# CH32V203C8T6-R1.net
KiCad netlist of a schematic drawn in Altium Designer
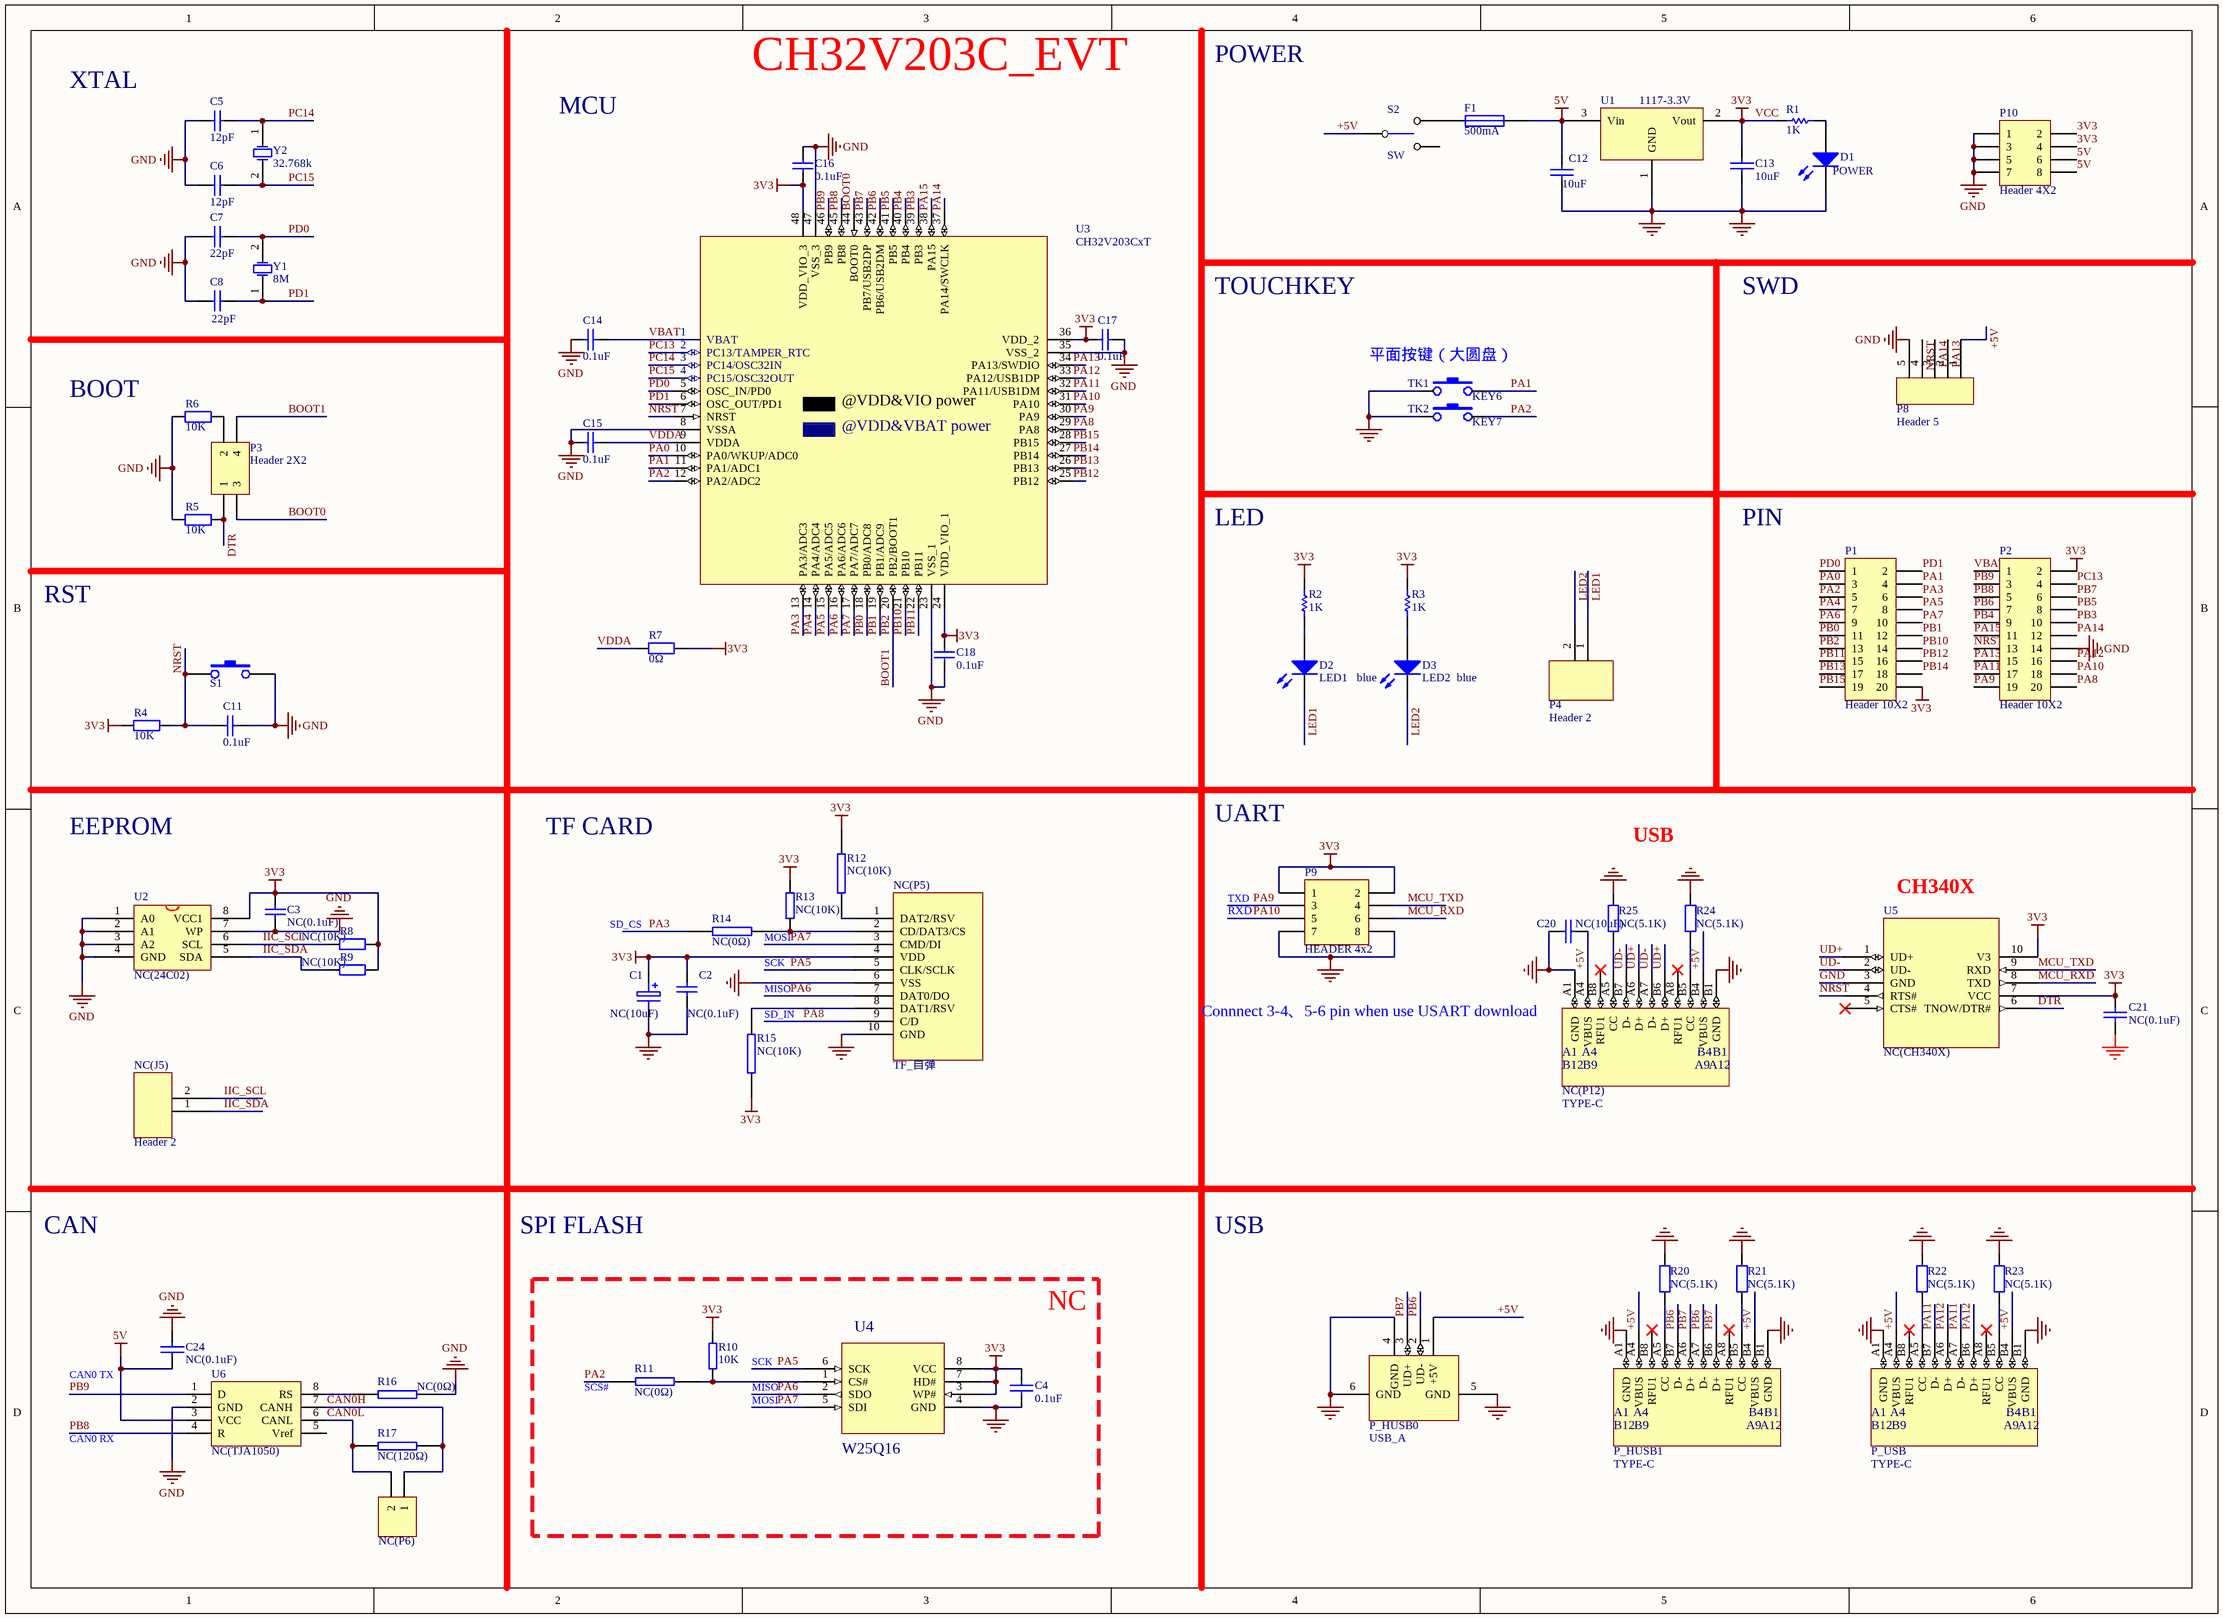
[diagram p0: CH32V203C8T6-R1.SchDoc]

(export (version "E")
  (design (tool "Eeschema 10.0.6"))
  (components
    (comp (ref "C1")
      (value "NC(10uF)")
      (footprint "3216")
      (description "Electrolytic Capacitor")
      (libsource (lib "*") (part "ELECTRO1"))
    )
    (comp (ref "C2")
      (value "NC(0.1uF)")
      (footprint "0603")
      (description "Capacitor")
      (fields (field (name "Comment") "0.1uF") (field (name "PUBLISHER") "Altium Limited"))
      (libsource (lib "*") (part "Cap"))
    )
    (comp (ref "C3")
      (value "NC(0.1uF)")
      (footprint "0603")
      (description "Capacitor")
      (fields (field (name "PUBLISHER") "Altium Limited"))
      (libsource (lib "Miscellaneous Devices") (part "Cap"))
    )
    (comp (ref "C4")
      (value "0.1uF")
      (footprint "0603")
      (description "Capacitor")
      (libsource (lib "") (part "CAP_1"))
    )
    (comp (ref "C5")
      (value "12pF")
      (footprint "0603")
      (description "Capacitor")
      (fields (field (name "PUBLISHER") "Altium Limited"))
      (libsource (lib "Miscellaneous Devices") (part "Cap"))
    )
    (comp (ref "C6")
      (value "12pF")
      (footprint "0603")
      (description "Capacitor")
      (fields (field (name "PUBLISHER") "Altium Limited"))
      (libsource (lib "Miscellaneous Devices") (part "Cap"))
    )
    (comp (ref "C7")
      (value "22pF")
      (footprint "0603")
      (description "Capacitor")
      (fields (field (name "PUBLISHER") "Altium Limited"))
      (libsource (lib "Miscellaneous Devices") (part "Cap"))
    )
    (comp (ref "C8")
      (value "22pF")
      (footprint "0603")
      (description "Capacitor")
      (fields (field (name "PUBLISHER") "Altium Limited"))
      (libsource (lib "Miscellaneous Devices") (part "Cap"))
    )
    (comp (ref "C11")
      (value "0.1uF")
      (footprint "0603")
      (description "Capacitor")
      (fields (field (name "PUBLISHER") "Altium Limited"))
      (libsource (lib "Miscellaneous Devices") (part "Cap"))
    )
    (comp (ref "C12")
      (value "10uF")
      (footprint "3216")
      (description "Capacitor")
      (libsource (lib "*") (part "CAP"))
    )
    (comp (ref "C13")
      (value "10uF")
      (footprint "0603")
      (description "Capacitor")
      (libsource (lib "*") (part "CAP"))
    )
    (comp (ref "C14")
      (value "0.1uF")
      (footprint "0603")
      (description "Capacitor")
      (fields (field (name "PUBLISHER") "Altium Limited"))
      (libsource (lib "Miscellaneous Devices") (part "Cap"))
    )
    (comp (ref "C15")
      (value "0.1uF")
      (footprint "0603")
      (description "Capacitor")
      (fields (field (name "PUBLISHER") "Altium Limited"))
      (libsource (lib "Miscellaneous Devices") (part "Cap"))
    )
    (comp (ref "C16")
      (value "0.1uF")
      (footprint "0603")
      (description "Capacitor")
      (fields (field (name "PUBLISHER") "Altium Limited"))
      (libsource (lib "Miscellaneous Devices") (part "Cap"))
    )
    (comp (ref "C17")
      (value "0.1uF")
      (footprint "0603")
      (description "Capacitor")
      (fields (field (name "PUBLISHER") "Altium Limited"))
      (libsource (lib "Miscellaneous Devices") (part "Cap"))
    )
    (comp (ref "C18")
      (value "0.1uF")
      (footprint "0603")
      (description "Capacitor")
      (fields (field (name "PUBLISHER") "Altium Limited"))
      (libsource (lib "Miscellaneous Devices") (part "Cap"))
    )
    (comp (ref "C20")
      (value "NC(10uF)")
      (footprint "3216_C")
      (description "Capacitor")
      (libsource (lib "*") (part "CAP"))
    )
    (comp (ref "C21")
      (value "NC(0.1uF)")
      (footprint "0603_C")
      (description "Capacitor")
      (libsource (lib "*") (part "CAP"))
    )
    (comp (ref "C24")
      (value "NC(0.1uF)")
      (footprint "0603")
      (description "Capacitor")
      (libsource (lib "") (part "CAP_1"))
    )
    (comp (ref "D1")
      (value "POWER")
      (footprint "0603L")
      (description "Typical INFRARED GaAs LED")
      (fields (field (name "PUBLISHER") "Altium Limited"))
      (libsource (lib "Miscellaneous Devices") (part "LED0"))
    )
    (comp (ref "D2")
      (value "LED1   blue")
      (footprint "0603L")
      (description "Typical INFRARED GaAs LED")
      (fields (field (name "PUBLISHER") "Altium Limited"))
      (libsource (lib "Miscellaneous Devices") (part "LED0"))
    )
    (comp (ref "D3")
      (value "LED2  blue")
      (footprint "0603L")
      (description "Typical INFRARED GaAs LED")
      (fields (field (name "PUBLISHER") "Altium Limited"))
      (libsource (lib "Miscellaneous Devices") (part "LED0"))
    )
    (comp (ref "F1")
      (value "500mA")
      (footprint "0603")
      (description "Fuse")
      (libsource (lib "*") (part "FUSE1"))
    )
    (comp (ref "NC(J5)") (value "Header 2") (footprint "SIP2 - 40mil") (libsource (lib "") (part "2HEAD_1")))
    (comp (ref "NC(P5)") (value "TF_自弹") (footprint "TF_CARD") (libsource (lib "*") (part "TF_自弹")))
    (comp (ref "NC(P6)")
      (value "Header 2")
      (footprint "PORT2 4.5MM")
      (description "Header, 2-Pin")
      (fields (field (name "PUBLISHER") "Altium Limited"))
      (libsource (lib "Miscellaneous Connectors") (part "Header 2"))
    )
    (comp (ref "NC(P12)")
      (value "TYPE-C")
      (footprint "TYPE-C-Receptacle-2.0")
      (libsource (lib "*") (part "TYPE-C1"))
    )
    (comp (ref "P1")
      (value "Header 10X2")
      (footprint "IDC20")
      (description "Header, 10-Pin, Dual row")
      (fields (field (name "PUBLISHER") "Altium Limited"))
      (libsource (lib "Miscellaneous Connectors") (part "Header 10X2"))
    )
    (comp (ref "P2")
      (value "Header 10X2")
      (footprint "IDC20")
      (description "Header, 10-Pin, Dual row")
      (fields (field (name "PUBLISHER") "Altium Limited"))
      (libsource (lib "Miscellaneous Connectors") (part "Header 10X2"))
    )
    (comp (ref "P3")
      (value "Header 2X2")
      (footprint "HDR2X2")
      (description "Header, 2-Pin, Dual row")
      (fields (field (name "PUBLISHER") "Altium Limited"))
      (libsource (lib "Miscellaneous Connectors") (part "Header 2X2"))
    )
    (comp (ref "P4") (value "Header 2") (footprint "SIP2 - 40mil") (libsource (lib "MYSCH") (part "2HEAD")))
    (comp (ref "P8")
      (value "Header 5")
      (footprint "SIP5 - 40mil")
      (libsource (lib "PCB_Project1") (part "2HEAD"))
    )
    (comp (ref "P9")
      (value "HEADER 4x2")
      (footprint "MYPCB:IDC8-2.54mm")
      (description "Header, 4-Pin, Dual row")
      (libsource (lib "wch_sch_others") (part "HEADER 4x2"))
    )
    (comp (ref "P10")
      (value "Header 4X2")
      (footprint "IDC8")
      (description "Header, 4-Pin, Dual row")
      (fields (field (name "PUBLISHER") "Altium Limited"))
      (libsource (lib "Miscellaneous Connectors") (part "Header 4X2"))
    )
    (comp (ref "P_HUSB0")
      (value "USB_A")
      (footprint "USBA-l")
      (description "USB Port")
      (libsource (lib "CHXXXSCH") (part "USB"))
    )
    (comp (ref "P_HUSB1")
      (value "TYPE-C")
      (footprint "TYPE-C-Receptacle-2.0")
      (libsource (lib "*") (part "TYPE-C1"))
    )
    (comp (ref "P_USB")
      (value "TYPE-C")
      (footprint "TYPE-C-Receptacle-2.0")
      (libsource (lib "*") (part "TYPE-C1"))
    )
    (comp (ref "R1")
      (value "1K")
      (footprint "0603")
      (description "Semiconductor Resistor")
      (fields (field (name "PUBLISHER") "Altium Limited"))
      (libsource (lib "Miscellaneous Devices") (part "Res Semi"))
    )
    (comp (ref "R2")
      (value "1K")
      (footprint "0603")
      (description "Semiconductor Resistor")
      (fields (field (name "PUBLISHER") "Altium Limited"))
      (libsource (lib "Miscellaneous Devices") (part "Res Semi"))
    )
    (comp (ref "R3")
      (value "1K")
      (footprint "0603")
      (description "Semiconductor Resistor")
      (fields (field (name "PUBLISHER") "Altium Limited"))
      (libsource (lib "Miscellaneous Devices") (part "Res Semi"))
    )
    (comp (ref "R4")
      (value "10K")
      (footprint "0603")
      (description "Resistor")
      (fields (field (name "PUBLISHER") "Altium Limited"))
      (libsource (lib "") (part "Res2_1"))
    )
    (comp (ref "R5")
      (value "10K")
      (footprint "0603")
      (description "Resistor")
      (fields (field (name "PUBLISHER") "Altium Limited"))
      (libsource (lib "") (part "Res2_1"))
    )
    (comp (ref "R6")
      (value "10K")
      (footprint "0603")
      (description "Resistor")
      (fields (field (name "PUBLISHER") "Altium Limited"))
      (libsource (lib "") (part "Res2_1"))
    )
    (comp (ref "R7")
      (value "0Ω")
      (footprint "0603")
      (description "Resistor")
      (fields (field (name "PUBLISHER") "Altium Limited"))
      (libsource (lib "") (part "Res2_1"))
    )
    (comp (ref "R8")
      (value "NC(10K)")
      (footprint "0603")
      (description "Resistor")
      (fields (field (name "PUBLISHER") "Altium Limited"))
      (libsource (lib "") (part "Res2_1"))
    )
    (comp (ref "R9")
      (value "NC(10K)")
      (footprint "0603")
      (description "Resistor")
      (fields (field (name "PUBLISHER") "Altium Limited"))
      (libsource (lib "") (part "Res2_1"))
    )
    (comp (ref "R10") (value "10K") (footprint "0603") (libsource (lib "*") (part "DZ")))
    (comp (ref "R11") (value "NC(0Ω)") (footprint "0603") (libsource (lib "*") (part "RES2")))
    (comp (ref "R12") (value "NC(10K)") (footprint "0603") (libsource (lib "*") (part "RES2")))
    (comp (ref "R13") (value "NC(10K)") (footprint "0603") (libsource (lib "*") (part "DZ")))
    (comp (ref "R14") (value "NC(0Ω)") (footprint "0603") (libsource (lib "*") (part "RES2")))
    (comp (ref "R15") (value "NC(10K)") (footprint "0603") (libsource (lib "*") (part "RES2")))
    (comp (ref "R16") (value "NC(0Ω)") (footprint "0603") (libsource (lib "*") (part "RES2")))
    (comp (ref "R17") (value "NC(120Ω)") (footprint "0603") (libsource (lib "*") (part "RES2")))
    (comp (ref "R20")
      (value "NC(5.1K)")
      (footprint "0603")
      (description "Resistor")
      (libsource (lib "Miscellaneous Devices") (part "Res2"))
    )
    (comp (ref "R21")
      (value "NC(5.1K)")
      (footprint "0603")
      (description "Resistor")
      (libsource (lib "Miscellaneous Devices") (part "Res2"))
    )
    (comp (ref "R22")
      (value "NC(5.1K)")
      (footprint "0603")
      (description "Resistor")
      (libsource (lib "Miscellaneous Devices") (part "Res2"))
    )
    (comp (ref "R23")
      (value "NC(5.1K)")
      (footprint "0603")
      (description "Resistor")
      (libsource (lib "Miscellaneous Devices") (part "Res2"))
    )
    (comp (ref "R24")
      (value "NC(5.1K)")
      (footprint "0603")
      (description "Resistor")
      (libsource (lib "Miscellaneous Devices") (part "Res2"))
    )
    (comp (ref "R25")
      (value "NC(5.1K)")
      (footprint "0603")
      (description "Resistor")
      (libsource (lib "Miscellaneous Devices") (part "Res2"))
    )
    (comp (ref "S1") (value "KEY") (footprint "贴片按键") (libsource (lib "CCDXPLIB") (part "KEY")))
    (comp (ref "S2") (value "SW") (footprint "KEY2") (libsource (lib "MYSCH") (part "SW")))
    (comp (ref "TK1") (value "KEY6") (footprint "KEY68") (libsource (lib "*") (part "KEY")))
    (comp (ref "TK2") (value "KEY7") (footprint "KEY68") (libsource (lib "*") (part "KEY")))
    (comp (ref "U1")
      (value "1117-3.3V")
      (footprint "SOT-223")
      (libsource (lib "wch_sch_others") (part "1117-3.3V"))
    )
    (comp (ref "U2") (value "NC(24C02)") (footprint "SOP8") (libsource (lib "Elite_SCH") (part "24C256")))
    (comp (ref "U3")
      (value "CH32V203CxT")
      (footprint "LQFP48")
      (description "RISC-V LMD-MCU, 144MHz, 2*USB FS, CAN")
      (libsource (lib "CHXXX") (part "CH32V203CxT"))
    )
    (comp (ref "U4")
      (value "W25Q16")
      (footprint "016 SO-8")
      (libsource (lib "*") (part "Pro89C.tmp_25F512_2"))
    )
    (comp (ref "U5")
      (value "NC(CH340X)")
      (footprint "MSOP10")
      (description "USB to TTL Serial / UART")
      (libsource (lib "CHXXX") (part "CH340X"))
    )
    (comp (ref "U6") (value "NC(TJA1050)") (footprint "SOP8") (libsource (lib "CAN") (part "Component_1")))
    (comp (ref "Y1")
      (value "8M")
      (footprint "XT62/28")
      (description "Crystal Oscillator")
      (fields (field (name "PUBLISHER") "Altium Limited"))
      (libsource (lib "Miscellaneous Devices") (part "XTAL"))
    )
    (comp (ref "Y2")
      (value "32.768k")
      (footprint "FC-135")
      (description "Crystal Oscillator")
      (fields (field (name "PUBLISHER") "Altium Limited"))
      (libsource (lib "Miscellaneous Devices") (part "XTAL"))
    )
  )
  (nets
    (net (code "1") (name "/+5V") (class "Default")
      (node (ref "C20") (pin "2") (pinfunction "2_2") (pintype "passive"))
      (node (ref "NC(P12)") (pin "A4") (pinfunction "VBUS_A4") (pintype "bidirectional"))
      (node (ref "NC(P12)") (pin "B4") (pinfunction "VBUS_B4") (pintype "bidirectional"))
      (node (ref "P8") (pin "1") (pintype "passive"))
      (node (ref "P_HUSB0") (pin "1") (pinfunction "+5V_1") (pintype "power_in"))
      (node (ref "P_HUSB1") (pin "A4") (pinfunction "VBUS_A4") (pintype "bidirectional"))
      (node (ref "P_HUSB1") (pin "B4") (pinfunction "VBUS_B4") (pintype "bidirectional"))
      (node (ref "P_USB") (pin "A4") (pinfunction "VBUS_A4") (pintype "bidirectional"))
      (node (ref "P_USB") (pin "B4") (pinfunction "VBUS_B4") (pintype "bidirectional"))
      (node (ref "S2") (pin "1") (pinfunction "1_1") (pintype "passive"))
    )
    (net (code "3") (name "/BOOT0") (class "Default")
      (node (ref "P3") (pin "3") (pinfunction "3_3") (pintype "passive"))
      (node (ref "U3") (pin "44") (pinfunction "BOOT0_44") (pintype "input"))
    )
    (net (code "4") (name "/BOOT1") (class "Default")
      (node (ref "P1") (pin "13") (pinfunction "13_13") (pintype "passive"))
      (node (ref "P3") (pin "4") (pinfunction "4_4") (pintype "passive"))
      (node (ref "U3") (pin "20") (pinfunction "PB2/BOOT1_20") (pintype "bidirectional"))
    )
    (net (code "5") (name "/CAN0H") (class "Default")
      (node (ref "NC(P6)") (pin "1") (pinfunction "1_1") (pintype "passive"))
      (node (ref "R17") (pin "1") (pinfunction "1_1") (pintype "passive"))
      (node (ref "U6") (pin "7") (pinfunction "CANH_7") (pintype "passive"))
    )
    (net (code "6") (name "/CAN0L") (class "Default")
      (node (ref "NC(P6)") (pin "2") (pinfunction "2_2") (pintype "passive"))
      (node (ref "R17") (pin "2") (pinfunction "2_2") (pintype "passive"))
      (node (ref "U6") (pin "6") (pinfunction "CANL_6") (pintype "passive"))
    )
    (net (code "7") (name "/DTR") (class "Default")
      (node (ref "P3") (pin "1") (pinfunction "1_1") (pintype "passive"))
      (node (ref "R5") (pin "1") (pinfunction "1_1") (pintype "passive"))
      (node (ref "U5") (pin "6") (pinfunction "TNOW/DTR#_6") (pintype "output"))
    )
    (net (code "8") (name "/IIC_SCL") (class "Default")
      (node (ref "NC(J5)") (pin "2") (pintype "passive"))
      (node (ref "R8") (pin "2") (pinfunction "2_2") (pintype "passive"))
      (node (ref "U2") (pin "6") (pinfunction "SCL_6") (pintype "passive"))
    )
    (net (code "9") (name "/IIC_SDA") (class "Default")
      (node (ref "NC(J5)") (pin "1") (pintype "passive"))
      (node (ref "R9") (pin "2") (pinfunction "2_2") (pintype "passive"))
      (node (ref "U2") (pin "5") (pinfunction "SDA_5") (pintype "passive"))
    )
    (net (code "10") (name "/LED1") (class "Default")
      (node (ref "D2") (pin "2") (pinfunction "K_2") (pintype "passive"))
      (node (ref "P4") (pin "1") (pintype "passive"))
    )
    (net (code "11") (name "/LED2") (class "Default")
      (node (ref "D3") (pin "2") (pinfunction "K_2") (pintype "passive"))
      (node (ref "P4") (pin "2") (pintype "passive"))
    )
    (net (code "12") (name "/MCU_RXD") (class "Default")
      (node (ref "P9") (pin "6") (pinfunction "6_6") (pintype "passive"))
      (node (ref "U5") (pin "8") (pinfunction "TXD_8") (pintype "output"))
    )
    (net (code "13") (name "/MCU_TXD") (class "Default")
      (node (ref "P9") (pin "4") (pinfunction "4_4") (pintype "passive"))
      (node (ref "U5") (pin "9") (pinfunction "RXD_9") (pintype "input"))
    )
    (net (code "14") (name "/NRST") (class "Default")
      (node (ref "C11") (pin "2") (pinfunction "2_2") (pintype "passive"))
      (node (ref "P2") (pin "13") (pinfunction "13_13") (pintype "passive"))
      (node (ref "P8") (pin "4") (pintype "passive"))
      (node (ref "R4") (pin "1") (pinfunction "1_1") (pintype "passive"))
      (node (ref "S1") (pin "1") (pinfunction "1_1") (pintype "passive"))
      (node (ref "U3") (pin "7") (pinfunction "NRST_7") (pintype "input"))
      (node (ref "U5") (pin "4") (pinfunction "RTS#_4") (pintype "output"))
    )
    (net (code "15") (name "/PA0") (class "Default")
      (node (ref "P1") (pin "3") (pinfunction "3_3") (pintype "passive"))
      (node (ref "U3") (pin "10") (pinfunction "PA0/WKUP/ADC0_10") (pintype "bidirectional"))
    )
    (net (code "16") (name "/PA1") (class "Default")
      (node (ref "P1") (pin "4") (pinfunction "4_4") (pintype "passive"))
      (node (ref "TK1") (pin "1") (pintype "passive"))
      (node (ref "U3") (pin "11") (pinfunction "PA1/ADC1_11") (pintype "bidirectional"))
    )
    (net (code "17") (name "/PA2") (class "Default")
      (node (ref "P1") (pin "5") (pinfunction "5_5") (pintype "passive"))
      (node (ref "R11") (pin "2") (pinfunction "2_2") (pintype "passive"))
      (node (ref "TK2") (pin "1") (pintype "passive"))
      (node (ref "U3") (pin "12") (pinfunction "PA2/ADC2_12") (pintype "bidirectional"))
    )
    (net (code "18") (name "/PA3") (class "Default")
      (node (ref "P1") (pin "6") (pinfunction "6_6") (pintype "passive"))
      (node (ref "R14") (pin "2") (pinfunction "2_2") (pintype "passive"))
      (node (ref "U3") (pin "13") (pinfunction "PA3/ADC3_13") (pintype "bidirectional"))
    )
    (net (code "19") (name "/PA4") (class "Default")
      (node (ref "P1") (pin "7") (pinfunction "7_7") (pintype "passive"))
      (node (ref "U3") (pin "14") (pinfunction "PA4/ADC4_14") (pintype "bidirectional"))
    )
    (net (code "20") (name "/PA5") (class "Default")
      (node (ref "NC(P5)") (pin "5") (pinfunction "CLK/SCLK_5") (pintype "passive"))
      (node (ref "P1") (pin "8") (pinfunction "8_8") (pintype "passive"))
      (node (ref "U3") (pin "15") (pinfunction "PA5/ADC5_15") (pintype "bidirectional"))
      (node (ref "U4") (pin "6") (pinfunction "SCK_6") (pintype "input"))
    )
    (net (code "21") (name "/PA6") (class "Default")
      (node (ref "NC(P5)") (pin "7") (pinfunction "DAT0/DO_7") (pintype "passive"))
      (node (ref "P1") (pin "9") (pinfunction "9_9") (pintype "passive"))
      (node (ref "U3") (pin "16") (pinfunction "PA6/ADC6_16") (pintype "bidirectional"))
      (node (ref "U4") (pin "2") (pinfunction "SDO_2") (pintype "output"))
    )
    (net (code "22") (name "/PA7") (class "Default")
      (node (ref "NC(P5)") (pin "3") (pinfunction "CMD/DI_3") (pintype "passive"))
      (node (ref "P1") (pin "10") (pinfunction "10_10") (pintype "passive"))
      (node (ref "U3") (pin "17") (pinfunction "PA7/ADC7_17") (pintype "bidirectional"))
      (node (ref "U4") (pin "5") (pinfunction "SDI_5") (pintype "input"))
    )
    (net (code "23") (name "/PA8") (class "Default")
      (node (ref "NC(P5)") (pin "9") (pinfunction "C/D_9") (pintype "passive"))
      (node (ref "P2") (pin "20") (pinfunction "20_20") (pintype "passive"))
      (node (ref "U3") (pin "29") (pinfunction "PA8_29") (pintype "bidirectional"))
    )
    (net (code "24") (name "/PA9") (class "Default")
      (node (ref "P2") (pin "19") (pinfunction "19_19") (pintype "passive"))
      (node (ref "P9") (pin "3") (pinfunction "3_3") (pintype "passive"))
      (node (ref "U3") (pin "30") (pinfunction "PA9_30") (pintype "bidirectional"))
    )
    (net (code "25") (name "/PA10") (class "Default")
      (node (ref "P2") (pin "18") (pinfunction "18_18") (pintype "passive"))
      (node (ref "P9") (pin "5") (pinfunction "5_5") (pintype "passive"))
      (node (ref "U3") (pin "31") (pinfunction "PA10_31") (pintype "bidirectional"))
    )
    (net (code "26") (name "/PA11") (class "Default")
      (node (ref "P2") (pin "17") (pinfunction "17_17") (pintype "passive"))
      (node (ref "P_USB") (pin "A7") (pinfunction "D-_A7") (pintype "bidirectional"))
      (node (ref "P_USB") (pin "B7") (pinfunction "D-_B7") (pintype "bidirectional"))
      (node (ref "U3") (pin "32") (pinfunction "PA11/USB1DM_32") (pintype "bidirectional"))
    )
    (net (code "27") (name "/PA12") (class "Default")
      (node (ref "P2") (pin "16") (pinfunction "16_16") (pintype "passive"))
      (node (ref "P_USB") (pin "A6") (pinfunction "D+_A6") (pintype "bidirectional"))
      (node (ref "P_USB") (pin "B6") (pinfunction "D+_B6") (pintype "bidirectional"))
      (node (ref "U3") (pin "33") (pinfunction "PA12/USB1DP_33") (pintype "bidirectional"))
    )
    (net (code "28") (name "/PA13") (class "Default")
      (node (ref "P2") (pin "15") (pinfunction "15_15") (pintype "passive"))
      (node (ref "P8") (pin "2") (pintype "passive"))
      (node (ref "U3") (pin "34") (pinfunction "PA13/SWDIO_34") (pintype "bidirectional"))
    )
    (net (code "29") (name "/PA14") (class "Default")
      (node (ref "P2") (pin "12") (pinfunction "12_12") (pintype "passive"))
      (node (ref "P8") (pin "3") (pintype "passive"))
      (node (ref "U3") (pin "37") (pinfunction "PA14/SWCLK_37") (pintype "bidirectional"))
    )
    (net (code "30") (name "/PA15") (class "Default")
      (node (ref "P2") (pin "11") (pinfunction "11_11") (pintype "passive"))
      (node (ref "U3") (pin "38") (pinfunction "PA15_38") (pintype "bidirectional"))
    )
    (net (code "31") (name "/PB0") (class "Default")
      (node (ref "P1") (pin "11") (pinfunction "11_11") (pintype "passive"))
      (node (ref "U3") (pin "18") (pinfunction "PB0/ADC8_18") (pintype "bidirectional"))
    )
    (net (code "32") (name "/PB1") (class "Default")
      (node (ref "P1") (pin "12") (pinfunction "12_12") (pintype "passive"))
      (node (ref "U3") (pin "19") (pinfunction "PB1/ADC9_19") (pintype "bidirectional"))
    )
    (net (code "33") (name "/PB3") (class "Default")
      (node (ref "P2") (pin "10") (pinfunction "10_10") (pintype "passive"))
      (node (ref "U3") (pin "39") (pinfunction "PB3_39") (pintype "bidirectional"))
    )
    (net (code "34") (name "/PB4") (class "Default")
      (node (ref "P2") (pin "9") (pinfunction "9_9") (pintype "passive"))
      (node (ref "U3") (pin "40") (pinfunction "PB4_40") (pintype "bidirectional"))
    )
    (net (code "35") (name "/PB5") (class "Default")
      (node (ref "P2") (pin "8") (pinfunction "8_8") (pintype "passive"))
      (node (ref "U3") (pin "41") (pinfunction "PB5_41") (pintype "bidirectional"))
    )
    (net (code "36") (name "/PB6") (class "Default")
      (node (ref "P2") (pin "7") (pinfunction "7_7") (pintype "passive"))
      (node (ref "P_HUSB0") (pin "2") (pinfunction "UD-_2") (pintype "bidirectional"))
      (node (ref "P_HUSB1") (pin "A7") (pinfunction "D-_A7") (pintype "bidirectional"))
      (node (ref "P_HUSB1") (pin "B7") (pinfunction "D-_B7") (pintype "bidirectional"))
      (node (ref "U3") (pin "42") (pinfunction "PB6/USB2DM_42") (pintype "bidirectional"))
    )
    (net (code "37") (name "/PB7") (class "Default")
      (node (ref "P2") (pin "6") (pinfunction "6_6") (pintype "passive"))
      (node (ref "P_HUSB0") (pin "3") (pinfunction "UD+_3") (pintype "bidirectional"))
      (node (ref "P_HUSB1") (pin "A6") (pinfunction "D+_A6") (pintype "bidirectional"))
      (node (ref "P_HUSB1") (pin "B6") (pinfunction "D+_B6") (pintype "bidirectional"))
      (node (ref "U3") (pin "43") (pinfunction "PB7/USB2DP_43") (pintype "bidirectional"))
    )
    (net (code "38") (name "/PB8") (class "Default")
      (node (ref "P2") (pin "5") (pinfunction "5_5") (pintype "passive"))
      (node (ref "U3") (pin "45") (pinfunction "PB8_45") (pintype "bidirectional"))
      (node (ref "U6") (pin "4") (pinfunction "R_4") (pintype "passive"))
    )
    (net (code "39") (name "/PB9") (class "Default")
      (node (ref "P2") (pin "3") (pinfunction "3_3") (pintype "passive"))
      (node (ref "U3") (pin "46") (pinfunction "PB9_46") (pintype "bidirectional"))
      (node (ref "U6") (pin "1") (pinfunction "D_1") (pintype "passive"))
    )
    (net (code "40") (name "/PB10") (class "Default")
      (node (ref "P1") (pin "14") (pinfunction "14_14") (pintype "passive"))
      (node (ref "U3") (pin "21") (pinfunction "PB10_21") (pintype "bidirectional"))
    )
    (net (code "41") (name "/PB11") (class "Default")
      (node (ref "P1") (pin "15") (pinfunction "15_15") (pintype "passive"))
      (node (ref "U3") (pin "22") (pinfunction "PB11_22") (pintype "bidirectional"))
    )
    (net (code "42") (name "/PB12") (class "Default")
      (node (ref "P1") (pin "16") (pinfunction "16_16") (pintype "passive"))
      (node (ref "U3") (pin "25") (pinfunction "PB12_25") (pintype "bidirectional"))
    )
    (net (code "43") (name "/PB13") (class "Default")
      (node (ref "P1") (pin "17") (pinfunction "17_17") (pintype "passive"))
      (node (ref "U3") (pin "26") (pinfunction "PB13_26") (pintype "bidirectional"))
    )
    (net (code "44") (name "/PB14") (class "Default")
      (node (ref "P1") (pin "18") (pinfunction "18_18") (pintype "passive"))
      (node (ref "U3") (pin "27") (pinfunction "PB14_27") (pintype "bidirectional"))
    )
    (net (code "45") (name "/PB15") (class "Default")
      (node (ref "P1") (pin "19") (pinfunction "19_19") (pintype "passive"))
      (node (ref "U3") (pin "28") (pinfunction "PB15_28") (pintype "bidirectional"))
    )
    (net (code "46") (name "/PC13") (class "Default")
      (node (ref "P2") (pin "4") (pinfunction "4_4") (pintype "passive"))
      (node (ref "U3") (pin "2") (pinfunction "PC13/TAMPER_RTC_2") (pintype "bidirectional"))
    )
    (net (code "47") (name "/PC14") (class "Default")
      (node (ref "C5") (pin "1") (pinfunction "1_1") (pintype "passive"))
      (node (ref "U3") (pin "3") (pinfunction "PC14/OSC32IN_3") (pintype "bidirectional"))
      (node (ref "Y2") (pin "1") (pinfunction "OSC1_1") (pintype "passive"))
    )
    (net (code "48") (name "/PC15") (class "Default")
      (node (ref "C6") (pin "1") (pinfunction "1_1") (pintype "passive"))
      (node (ref "U3") (pin "4") (pinfunction "PC15/OSC32OUT_4") (pintype "bidirectional"))
      (node (ref "Y2") (pin "2") (pinfunction "OSC2_2") (pintype "passive"))
    )
    (net (code "49") (name "/PD0") (class "Default")
      (node (ref "C7") (pin "2") (pinfunction "2_2") (pintype "passive"))
      (node (ref "P1") (pin "1") (pinfunction "1_1") (pintype "passive"))
      (node (ref "U3") (pin "5") (pinfunction "OSC_IN/PD0_5") (pintype "bidirectional"))
      (node (ref "Y1") (pin "2") (pinfunction "OSC2_2") (pintype "passive"))
    )
    (net (code "50") (name "/PD1") (class "Default")
      (node (ref "C8") (pin "2") (pinfunction "2_2") (pintype "passive"))
      (node (ref "P1") (pin "2") (pinfunction "2_2") (pintype "passive"))
      (node (ref "U3") (pin "6") (pinfunction "OSC_OUT/PD1_6") (pintype "bidirectional"))
      (node (ref "Y1") (pin "1") (pinfunction "OSC1_1") (pintype "passive"))
    )
    (net (code "51") (name "/UD+") (class "Default")
      (node (ref "NC(P12)") (pin "A6") (pinfunction "D+_A6") (pintype "bidirectional"))
      (node (ref "NC(P12)") (pin "B6") (pinfunction "D+_B6") (pintype "bidirectional"))
      (node (ref "U5") (pin "1") (pinfunction "UD+_1") (pintype "bidirectional"))
    )
    (net (code "52") (name "/UD-") (class "Default")
      (node (ref "NC(P12)") (pin "A7") (pinfunction "D-_A7") (pintype "bidirectional"))
      (node (ref "NC(P12)") (pin "B7") (pinfunction "D-_B7") (pintype "bidirectional"))
      (node (ref "U5") (pin "2") (pinfunction "UD-_2") (pintype "bidirectional"))
    )
    (net (code "53") (name "/VBAT") (class "Default")
      (node (ref "C14") (pin "1") (pinfunction "1_1") (pintype "passive"))
      (node (ref "P2") (pin "1") (pinfunction "1_1") (pintype "passive"))
      (node (ref "U3") (pin "1") (pinfunction "VBAT_1") (pintype "power_in"))
    )
    (net (code "54") (name "/VDDA") (class "Default")
      (node (ref "C15") (pin "1") (pinfunction "1_1") (pintype "passive"))
      (node (ref "R7") (pin "2") (pinfunction "2_2") (pintype "passive"))
      (node (ref "U3") (pin "9") (pinfunction "VDDA_9") (pintype "power_in"))
    )
    (net (code "55") (name "3V3") (class "Default")
      (node (ref "C1") (pin "1") (pinfunction "1_1") (pintype "passive"))
      (node (ref "C13") (pin "1") (pinfunction "1_1") (pintype "passive"))
      (node (ref "C16") (pin "2") (pinfunction "2_2") (pintype "passive"))
      (node (ref "C17") (pin "2") (pinfunction "2_2") (pintype "passive"))
      (node (ref "C18") (pin "2") (pinfunction "2_2") (pintype "passive"))
      (node (ref "C2") (pin "1") (pinfunction "1_1") (pintype "passive"))
      (node (ref "C21") (pin "1") (pinfunction "1_1") (pintype "passive"))
      (node (ref "C3") (pin "2") (pinfunction "2_2") (pintype "passive"))
      (node (ref "C4") (pin "2") (pinfunction "2_2") (pintype "passive"))
      (node (ref "NC(P5)") (pin "4") (pinfunction "VDD_4") (pintype "passive"))
      (node (ref "P1") (pin "20") (pinfunction "20_20") (pintype "passive"))
      (node (ref "P10") (pin "2") (pinfunction "2_2") (pintype "passive"))
      (node (ref "P10") (pin "4") (pinfunction "4_4") (pintype "passive"))
      (node (ref "P2") (pin "2") (pinfunction "2_2") (pintype "passive"))
      (node (ref "P9") (pin "1") (pinfunction "1_1") (pintype "passive"))
      (node (ref "P9") (pin "2") (pinfunction "2_2") (pintype "passive"))
      (node (ref "R1") (pin "2") (pinfunction "2_2") (pintype "passive"))
      (node (ref "R10") (pin "2") (pintype "passive"))
      (node (ref "R12") (pin "2") (pinfunction "2_2") (pintype "passive"))
      (node (ref "R13") (pin "2") (pintype "passive"))
      (node (ref "R15") (pin "1") (pinfunction "1_1") (pintype "passive"))
      (node (ref "R2") (pin "1") (pinfunction "1_1") (pintype "passive"))
      (node (ref "R3") (pin "1") (pinfunction "1_1") (pintype "passive"))
      (node (ref "R4") (pin "2") (pinfunction "2_2") (pintype "passive"))
      (node (ref "R7") (pin "1") (pinfunction "1_1") (pintype "passive"))
      (node (ref "R8") (pin "1") (pinfunction "1_1") (pintype "passive"))
      (node (ref "R9") (pin "1") (pinfunction "1_1") (pintype "passive"))
      (node (ref "U1") (pin "2") (pinfunction "Vout_2") (pintype "passive"))
      (node (ref "U2") (pin "8") (pinfunction "VCC1_8") (pintype "passive"))
      (node (ref "U3") (pin "24") (pinfunction "VDD_VIO_1_24") (pintype "power_in"))
      (node (ref "U3") (pin "36") (pinfunction "VDD_2_36") (pintype "power_in"))
      (node (ref "U3") (pin "48") (pinfunction "VDD_VIO_3_48") (pintype "power_in"))
      (node (ref "U4") (pin "3") (pinfunction "WP#_3") (pintype "input"))
      (node (ref "U4") (pin "7") (pinfunction "HD#_7") (pintype "power_in"))
      (node (ref "U4") (pin "8") (pinfunction "VCC_8") (pintype "power_in"))
      (node (ref "U5") (pin "10") (pinfunction "V3_10") (pintype "power_in"))
      (node (ref "U5") (pin "7") (pinfunction "VCC_7") (pintype "power_in"))
    )
    (net (code "56") (name "5V") (class "Default")
      (node (ref "C12") (pin "1") (pinfunction "1_1") (pintype "passive"))
      (node (ref "C24") (pin "2") (pinfunction "2_2") (pintype "passive"))
      (node (ref "F1") (pin "2") (pinfunction "2_2") (pintype "passive"))
      (node (ref "P10") (pin "6") (pinfunction "6_6") (pintype "passive"))
      (node (ref "P10") (pin "8") (pinfunction "8_8") (pintype "passive"))
      (node (ref "U1") (pin "3") (pinfunction "Vin_3") (pintype "passive"))
      (node (ref "U6") (pin "3") (pinfunction "VCC_3") (pintype "passive"))
    )
    (net (code "57") (name "GND") (class "Default")
      (node (ref "C1") (pin "2") (pinfunction "2_2") (pintype "passive"))
      (node (ref "C11") (pin "1") (pinfunction "1_1") (pintype "passive"))
      (node (ref "C12") (pin "2") (pinfunction "2_2") (pintype "passive"))
      (node (ref "C13") (pin "2") (pinfunction "2_2") (pintype "passive"))
      (node (ref "C14") (pin "2") (pinfunction "2_2") (pintype "passive"))
      (node (ref "C15") (pin "2") (pinfunction "2_2") (pintype "passive"))
      (node (ref "C16") (pin "1") (pinfunction "1_1") (pintype "passive"))
      (node (ref "C17") (pin "1") (pinfunction "1_1") (pintype "passive"))
      (node (ref "C18") (pin "1") (pinfunction "1_1") (pintype "passive"))
      (node (ref "C2") (pin "2") (pinfunction "2_2") (pintype "passive"))
      (node (ref "C20") (pin "1") (pinfunction "1_1") (pintype "passive"))
      (node (ref "C21") (pin "2") (pinfunction "2_2") (pintype "passive"))
      (node (ref "C24") (pin "1") (pinfunction "1_1") (pintype "passive"))
      (node (ref "C3") (pin "1") (pinfunction "1_1") (pintype "passive"))
      (node (ref "C4") (pin "1") (pinfunction "1_1") (pintype "passive"))
      (node (ref "C5") (pin "2") (pinfunction "2_2") (pintype "passive"))
      (node (ref "C6") (pin "2") (pinfunction "2_2") (pintype "passive"))
      (node (ref "C7") (pin "1") (pinfunction "1_1") (pintype "passive"))
      (node (ref "C8") (pin "1") (pinfunction "1_1") (pintype "passive"))
      (node (ref "D1") (pin "2") (pinfunction "K_2") (pintype "passive"))
      (node (ref "NC(P12)") (pin "A1") (pinfunction "GND_A1") (pintype "bidirectional"))
      (node (ref "NC(P12)") (pin "B1") (pinfunction "GND_B1") (pintype "bidirectional"))
      (node (ref "NC(P5)") (pin "10") (pinfunction "GND_10") (pintype "passive"))
      (node (ref "NC(P5)") (pin "6") (pinfunction "VSS_6") (pintype "passive"))
      (node (ref "P10") (pin "1") (pinfunction "1_1") (pintype "passive"))
      (node (ref "P10") (pin "3") (pinfunction "3_3") (pintype "passive"))
      (node (ref "P10") (pin "5") (pinfunction "5_5") (pintype "passive"))
      (node (ref "P10") (pin "7") (pinfunction "7_7") (pintype "passive"))
      (node (ref "P2") (pin "14") (pinfunction "14_14") (pintype "passive"))
      (node (ref "P8") (pin "5") (pintype "passive"))
      (node (ref "P9") (pin "7") (pinfunction "7_7") (pintype "passive"))
      (node (ref "P9") (pin "8") (pinfunction "8_8") (pintype "passive"))
      (node (ref "P_HUSB0") (pin "4") (pinfunction "GND_4") (pintype "power_in"))
      (node (ref "P_HUSB0") (pin "5") (pinfunction "GND_5") (pintype "power_in"))
      (node (ref "P_HUSB0") (pin "6") (pinfunction "GND_6") (pintype "power_in"))
      (node (ref "P_HUSB1") (pin "A1") (pinfunction "GND_A1") (pintype "bidirectional"))
      (node (ref "P_HUSB1") (pin "B1") (pinfunction "GND_B1") (pintype "bidirectional"))
      (node (ref "P_USB") (pin "A1") (pinfunction "GND_A1") (pintype "bidirectional"))
      (node (ref "P_USB") (pin "B1") (pinfunction "GND_B1") (pintype "bidirectional"))
      (node (ref "R16") (pin "1") (pinfunction "1_1") (pintype "passive"))
      (node (ref "R20") (pin "2") (pinfunction "2_2") (pintype "passive"))
      (node (ref "R21") (pin "2") (pinfunction "2_2") (pintype "passive"))
      (node (ref "R22") (pin "2") (pinfunction "2_2") (pintype "passive"))
      (node (ref "R23") (pin "2") (pinfunction "2_2") (pintype "passive"))
      (node (ref "R24") (pin "2") (pinfunction "2_2") (pintype "passive"))
      (node (ref "R25") (pin "2") (pinfunction "2_2") (pintype "passive"))
      (node (ref "R5") (pin "2") (pinfunction "2_2") (pintype "passive"))
      (node (ref "R6") (pin "2") (pinfunction "2_2") (pintype "passive"))
      (node (ref "S1") (pin "3") (pinfunction "3_3") (pintype "passive"))
      (node (ref "TK1") (pin "3") (pintype "passive"))
      (node (ref "TK2") (pin "3") (pintype "passive"))
      (node (ref "U1") (pin "1") (pinfunction "GND_1") (pintype "passive"))
      (node (ref "U2") (pin "1") (pinfunction "A0_1") (pintype "passive"))
      (node (ref "U2") (pin "2") (pinfunction "A1_2") (pintype "passive"))
      (node (ref "U2") (pin "3") (pinfunction "A2_3") (pintype "passive"))
      (node (ref "U2") (pin "4") (pinfunction "GND_4") (pintype "passive"))
      (node (ref "U2") (pin "7") (pinfunction "WP_7") (pintype "passive"))
      (node (ref "U3") (pin "23") (pinfunction "VSS_1_23") (pintype "power_in"))
      (node (ref "U3") (pin "35") (pinfunction "VSS_2_35") (pintype "power_in"))
      (node (ref "U3") (pin "47") (pinfunction "VSS_3_47") (pintype "power_in"))
      (node (ref "U3") (pin "8") (pinfunction "VSSA_8") (pintype "power_in"))
      (node (ref "U4") (pin "4") (pinfunction "GND_4") (pintype "power_in"))
      (node (ref "U5") (pin "3") (pinfunction "GND_3") (pintype "power_in"))
      (node (ref "U6") (pin "2") (pinfunction "GND_2") (pintype "passive"))
    )
    (net (code "58") (name "Net-(D1-A)") (class "Default")
      (node (ref "D1") (pin "1") (pinfunction "A_1") (pintype "passive"))
      (node (ref "R1") (pin "1") (pinfunction "1_1") (pintype "passive"))
    )
    (net (code "59") (name "Net-(D2-A)") (class "Default")
      (node (ref "D2") (pin "1") (pinfunction "A_1") (pintype "passive"))
      (node (ref "R2") (pin "2") (pinfunction "2_2") (pintype "passive"))
    )
    (net (code "60") (name "Net-(D3-A)") (class "Default")
      (node (ref "D3") (pin "1") (pinfunction "A_1") (pintype "passive"))
      (node (ref "R3") (pin "2") (pinfunction "2_2") (pintype "passive"))
    )
    (net (code "61") (name "Net-(F1-Pad1)") (class "Default")
      (node (ref "F1") (pin "1") (pinfunction "1_1") (pintype "passive"))
      (node (ref "S2") (pin "2") (pinfunction "2_2") (pintype "passive"))
    )
    (net (code "62") (name "Net-(NC(P5)-CD{slash}DAT3{slash}CS)") (class "Default")
      (node (ref "NC(P5)") (pin "2") (pinfunction "CD/DAT3/CS_2") (pintype "passive"))
      (node (ref "R13") (pin "1") (pintype "passive"))
      (node (ref "R14") (pin "1") (pinfunction "1_1") (pintype "passive"))
    )
    (net (code "63") (name "Net-(NC(P5)-DAT1{slash}RSV)") (class "Default")
      (node (ref "NC(P5)") (pin "8") (pinfunction "DAT1/RSV_8") (pintype "passive"))
      (node (ref "R15") (pin "2") (pinfunction "2_2") (pintype "passive"))
    )
    (net (code "64") (name "Net-(NC(P5)-DAT2{slash}RSV)") (class "Default")
      (node (ref "NC(P5)") (pin "1") (pinfunction "DAT2/RSV_1") (pintype "passive"))
      (node (ref "R12") (pin "1") (pinfunction "1_1") (pintype "passive"))
    )
    (net (code "65") (name "Net-(NC(P12)-CC-PadA5)") (class "Default")
      (node (ref "NC(P12)") (pin "A5") (pinfunction "CC_A5") (pintype "bidirectional"))
      (node (ref "R25") (pin "1") (pinfunction "1_1") (pintype "passive"))
    )
    (net (code "66") (name "Net-(NC(P12)-CC-PadB5)") (class "Default")
      (node (ref "NC(P12)") (pin "B5") (pinfunction "CC_B5") (pintype "bidirectional"))
      (node (ref "R24") (pin "1") (pinfunction "1_1") (pintype "passive"))
    )
    (net (code "67") (name "Net-(P3-Pad2)") (class "Default")
      (node (ref "P3") (pin "2") (pinfunction "2_2") (pintype "passive"))
      (node (ref "R6") (pin "1") (pinfunction "1_1") (pintype "passive"))
    )
    (net (code "68") (name "Net-(P_HUSB1-CC-PadA5)") (class "Default")
      (node (ref "P_HUSB1") (pin "A5") (pinfunction "CC_A5") (pintype "bidirectional"))
      (node (ref "R20") (pin "1") (pinfunction "1_1") (pintype "passive"))
    )
    (net (code "69") (name "Net-(P_HUSB1-CC-PadB5)") (class "Default")
      (node (ref "P_HUSB1") (pin "B5") (pinfunction "CC_B5") (pintype "bidirectional"))
      (node (ref "R21") (pin "1") (pinfunction "1_1") (pintype "passive"))
    )
    (net (code "70") (name "Net-(P_USB-CC-PadA5)") (class "Default")
      (node (ref "P_USB") (pin "A5") (pinfunction "CC_A5") (pintype "bidirectional"))
      (node (ref "R22") (pin "1") (pinfunction "1_1") (pintype "passive"))
    )
    (net (code "71") (name "Net-(P_USB-CC-PadB5)") (class "Default")
      (node (ref "P_USB") (pin "B5") (pinfunction "CC_B5") (pintype "bidirectional"))
      (node (ref "R23") (pin "1") (pinfunction "1_1") (pintype "passive"))
    )
    (net (code "72") (name "Net-(U4-CS#)") (class "Default")
      (node (ref "R10") (pin "1") (pintype "passive"))
      (node (ref "R11") (pin "1") (pinfunction "1_1") (pintype "passive"))
      (node (ref "U4") (pin "1") (pinfunction "CS#_1") (pintype "input"))
    )
    (net (code "73") (name "Net-(U6-RS)") (class "Default")
      (node (ref "R16") (pin "2") (pinfunction "2_2") (pintype "passive"))
      (node (ref "U6") (pin "8") (pinfunction "RS_8") (pintype "passive"))
    )
    (net (code "74") (name "unconnected-(NC(P12)-RFU1-PadA8)") (class "Default")
      (node (ref "NC(P12)") (pin "A8") (pinfunction "RFU1_A8") (pintype "bidirectional+no_connect"))
    )
    (net (code "75") (name "unconnected-(NC(P12)-RFU1-PadB8)") (class "Default")
      (node (ref "NC(P12)") (pin "B8") (pinfunction "RFU1_B8") (pintype "bidirectional+no_connect"))
    )
    (net (code "76") (name "unconnected-(P_HUSB1-RFU1-PadA8)") (class "Default")
      (node (ref "P_HUSB1") (pin "A8") (pinfunction "RFU1_A8") (pintype "bidirectional+no_connect"))
    )
    (net (code "77") (name "unconnected-(P_HUSB1-RFU1-PadB8)") (class "Default")
      (node (ref "P_HUSB1") (pin "B8") (pinfunction "RFU1_B8") (pintype "bidirectional+no_connect"))
    )
    (net (code "78") (name "unconnected-(P_USB-RFU1-PadA8)") (class "Default")
      (node (ref "P_USB") (pin "A8") (pinfunction "RFU1_A8") (pintype "bidirectional+no_connect"))
    )
    (net (code "79") (name "unconnected-(P_USB-RFU1-PadB8)") (class "Default")
      (node (ref "P_USB") (pin "B8") (pinfunction "RFU1_B8") (pintype "bidirectional+no_connect"))
    )
    (net (code "80") (name "unconnected-(S2-Pad3)") (class "Default")
      (node (ref "S2") (pin "3") (pinfunction "3_3") (pintype "passive"))
    )
    (net (code "81") (name "unconnected-(U5-CTS#-Pad5)") (class "Default")
      (node (ref "U5") (pin "5") (pinfunction "CTS#_5") (pintype "input+no_connect"))
    )
    (net (code "82") (name "unconnected-(U6-Vref-Pad5)") (class "Default")
      (node (ref "U6") (pin "5") (pinfunction "Vref_5") (pintype "passive"))
    )
  )
)
